# ControlMoteur_ESP32.net
KiCad netlist of a schematic drawn in EasyEDA
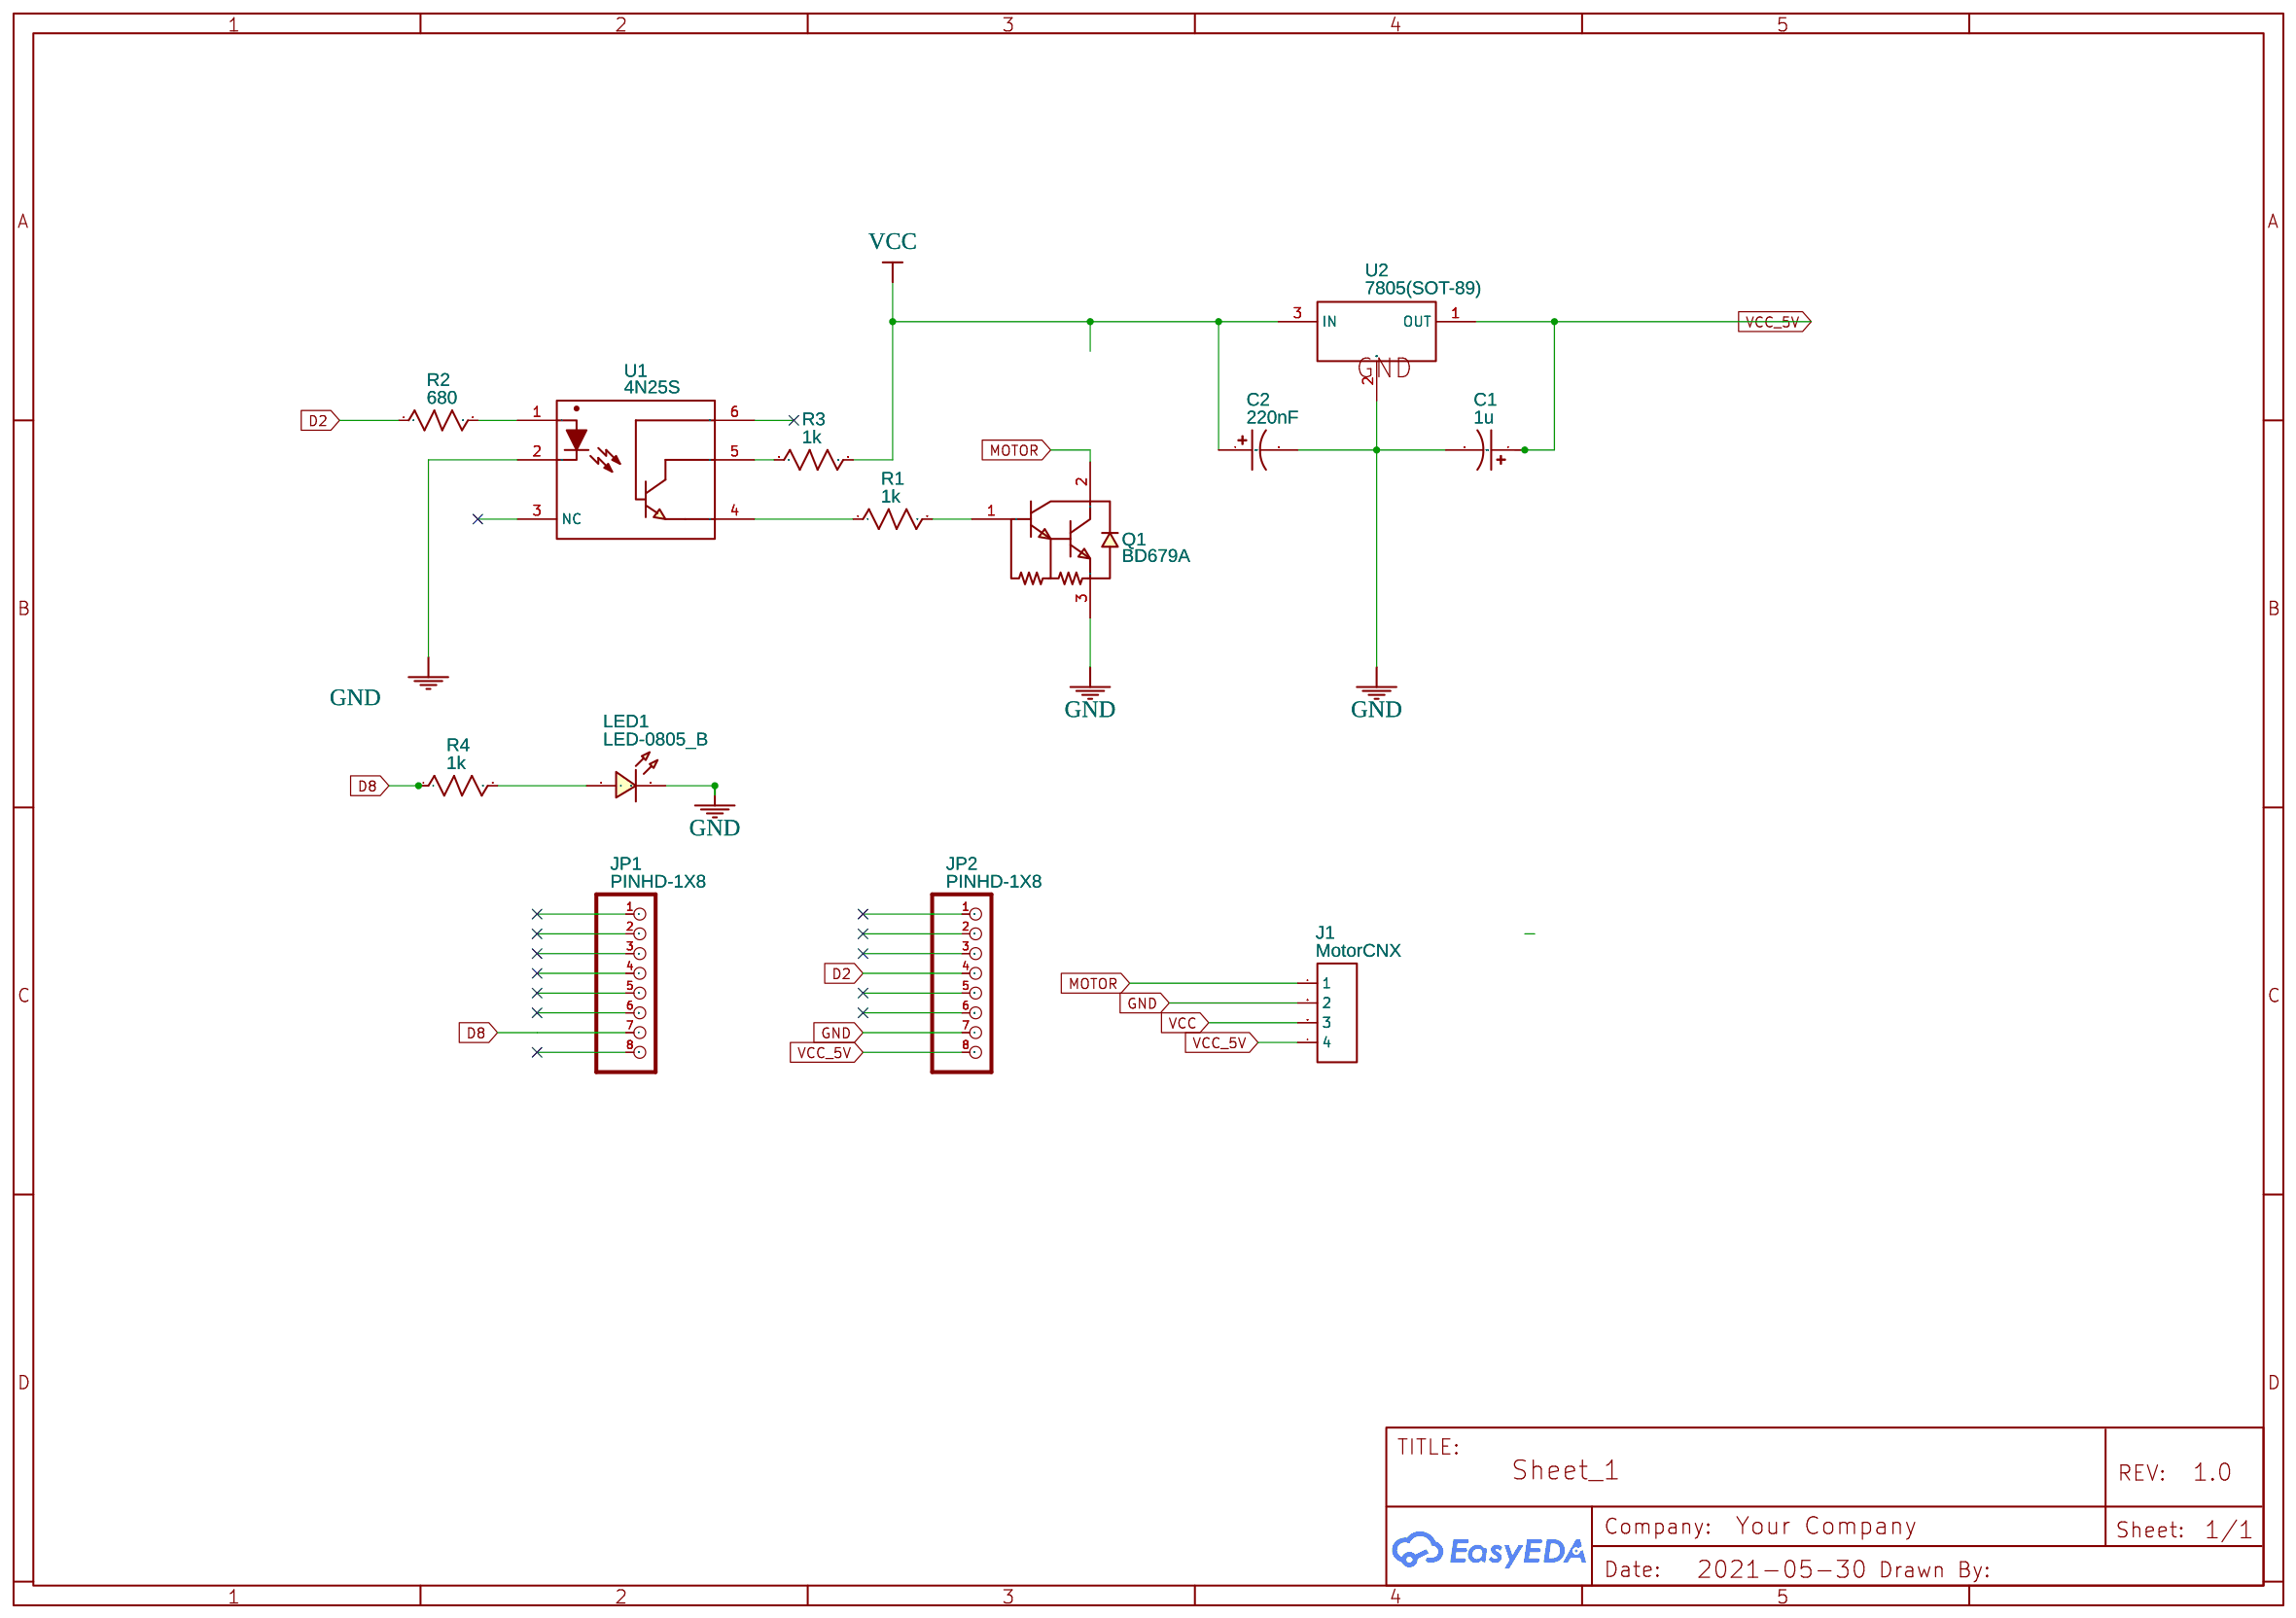
[diagram p0: schematic sheet]

(export (version "E")
  (design (tool "Eeschema 10.0.6"))
  (components
    (comp (ref "C1") (value "1u") (libsource (lib "") (part "C_Tan_SMD_A_US_1")))
    (comp (ref "C2") (value "220nF") (libsource (lib "") (part "C_Tan_SMD_A_US")))
    (comp (ref "J1")
      (value "MotorCNX")
      (fields (field (name "BOM_Supplier Part") "C124378"))
      (libsource (lib "") (part "HDR-M-2.54_1x4"))
    )
    (comp (ref "JP1")
      (value "PINHD-1X8")
      (fields (field (name "BOM_Supplier Part") "C492407"))
      (libsource (lib "") (part "PINHD-1X8"))
    )
    (comp (ref "JP2")
      (value "PINHD-1X8")
      (fields (field (name "BOM_Supplier Part") "C492407"))
      (libsource (lib "") (part "PINHD-1X8"))
    )
    (comp (ref "LED1")
      (value "LED-0805_B")
      (fields
        (field (name "BOM_Manufacturer Part") "D-B080508B1-KS2")
        (field (name "BOM_Supplier Part") "C108412")
      )
      (libsource (lib "") (part "LED-0805_B"))
    )
    (comp (ref "Q1")
      (value "BD679A")
      (fields (field (name "BOM_Supplier Part") "C2760771"))
      (libsource (lib "") (part "BD679A"))
    )
    (comp (ref "R1") (value "1k") (libsource (lib "") (part "R_1210_US")))
    (comp (ref "R2") (value "680") (libsource (lib "") (part "R_1210_US")))
    (comp (ref "R3") (value "1k") (libsource (lib "") (part "R_1210_US")))
    (comp (ref "R4") (value "1k") (libsource (lib "") (part "R_1210_US")))
    (comp (ref "U1")
      (value "4N25S")
      (fields (field (name "BOM_Supplier Part") "C143074"))
      (libsource (lib "") (part "4N25S"))
    )
    (comp (ref "U2")
      (value "7805(SOT-89)")
      (fields (field (name "BOM_Manufacturer Part") "CJ78L05") (field (name "BOM_Supplier Part") "C2079"))
      (libsource (lib "") (part "7805(SOT-89)"))
    )
  )
  (nets
    (net (code "1") (name "D2") (class "Default")
      (node (ref "JP2") (pin "4") (pinfunction "4_4") (pintype "unspecified"))
      (node (ref "R2") (pin "1") (pinfunction "1_1") (pintype "unspecified"))
    )
    (net (code "2") (name "D8") (class "Default")
      (node (ref "JP1") (pin "7") (pinfunction "7_7") (pintype "unspecified"))
      (node (ref "R4") (pin "1") (pinfunction "1_1") (pintype "unspecified"))
    )
    (net (code "3") (name "GND") (class "Default")
      (node (ref "C1") (pin "2") (pinfunction "2_2") (pintype "unspecified"))
      (node (ref "C2") (pin "2") (pinfunction "2_2") (pintype "unspecified"))
      (node (ref "J1") (pin "2") (pinfunction "2_2") (pintype "unspecified"))
      (node (ref "JP2") (pin "7") (pinfunction "7_7") (pintype "unspecified"))
      (node (ref "LED1") (pin "2") (pinfunction "2_2") (pintype "unspecified"))
      (node (ref "Q1") (pin "3") (pinfunction "E_3") (pintype "unspecified"))
      (node (ref "U1") (pin "2") (pinfunction "CAT_2") (pintype "unspecified"))
      (node (ref "U2") (pin "2") (pinfunction "GND_2") (pintype "passive"))
    )
    (net (code "4") (name "MOTOR") (class "Default")
      (node (ref "J1") (pin "1") (pinfunction "1_1") (pintype "unspecified"))
      (node (ref "Q1") (pin "2") (pinfunction "C_2") (pintype "unspecified"))
    )
    (net (code "5") (name "Net-(LED1-Pad1)") (class "Default")
      (node (ref "LED1") (pin "1") (pinfunction "1_1") (pintype "unspecified"))
      (node (ref "R4") (pin "2") (pinfunction "2_2") (pintype "unspecified"))
    )
    (net (code "6") (name "Net-(Q1-B)") (class "Default")
      (node (ref "Q1") (pin "1") (pinfunction "B_1") (pintype "unspecified"))
      (node (ref "R1") (pin "2") (pinfunction "2_2") (pintype "unspecified"))
    )
    (net (code "7") (name "Net-(R1-Pad1)") (class "Default")
      (node (ref "R1") (pin "1") (pinfunction "1_1") (pintype "unspecified"))
      (node (ref "U1") (pin "4") (pinfunction "4_4") (pintype "unspecified"))
    )
    (net (code "8") (name "Net-(R2-Pad2)") (class "Default")
      (node (ref "R2") (pin "2") (pinfunction "2_2") (pintype "unspecified"))
      (node (ref "U1") (pin "1") (pinfunction "1_1") (pintype "unspecified"))
    )
    (net (code "9") (name "Net-(U1-GND)") (class "Default")
      (node (ref "R3") (pin "1") (pinfunction "1_1") (pintype "unspecified"))
      (node (ref "U1") (pin "5") (pinfunction "GND_5") (pintype "unspecified"))
    )
    (net (code "10") (name "VCC") (class "Default")
      (node (ref "C2") (pin "1") (pinfunction "1_1") (pintype "unspecified"))
      (node (ref "J1") (pin "3") (pinfunction "3_3") (pintype "unspecified"))
      (node (ref "R3") (pin "2") (pinfunction "2_2") (pintype "unspecified"))
      (node (ref "U2") (pin "3") (pinfunction "IN_3") (pintype "passive"))
    )
    (net (code "11") (name "VCC_5V") (class "Default")
      (node (ref "C1") (pin "1") (pinfunction "1_1") (pintype "unspecified"))
      (node (ref "J1") (pin "4") (pinfunction "4_4") (pintype "unspecified"))
      (node (ref "JP2") (pin "8") (pinfunction "8_8") (pintype "unspecified"))
      (node (ref "U2") (pin "1") (pinfunction "OUT_1") (pintype "passive"))
    )
    (net (code "12") (name "unconnected-(JP1-Pad1)") (class "Default")
      (node (ref "JP1") (pin "1") (pinfunction "1_1") (pintype "unspecified+no_connect"))
    )
    (net (code "13") (name "unconnected-(JP1-Pad2)") (class "Default")
      (node (ref "JP1") (pin "2") (pinfunction "2_2") (pintype "unspecified+no_connect"))
    )
    (net (code "14") (name "unconnected-(JP1-Pad3)") (class "Default")
      (node (ref "JP1") (pin "3") (pinfunction "3_3") (pintype "unspecified+no_connect"))
    )
    (net (code "15") (name "unconnected-(JP1-Pad4)") (class "Default")
      (node (ref "JP1") (pin "4") (pinfunction "4_4") (pintype "unspecified+no_connect"))
    )
    (net (code "16") (name "unconnected-(JP1-Pad5)") (class "Default")
      (node (ref "JP1") (pin "5") (pinfunction "5_5") (pintype "unspecified+no_connect"))
    )
    (net (code "17") (name "unconnected-(JP1-Pad6)") (class "Default")
      (node (ref "JP1") (pin "6") (pinfunction "6_6") (pintype "unspecified+no_connect"))
    )
    (net (code "18") (name "unconnected-(JP1-Pad8)") (class "Default")
      (node (ref "JP1") (pin "8") (pinfunction "8_8") (pintype "unspecified+no_connect"))
    )
    (net (code "19") (name "unconnected-(JP2-Pad1)") (class "Default")
      (node (ref "JP2") (pin "1") (pinfunction "1_1") (pintype "unspecified+no_connect"))
    )
    (net (code "20") (name "unconnected-(JP2-Pad2)") (class "Default")
      (node (ref "JP2") (pin "2") (pinfunction "2_2") (pintype "unspecified+no_connect"))
    )
    (net (code "21") (name "unconnected-(JP2-Pad3)") (class "Default")
      (node (ref "JP2") (pin "3") (pinfunction "3_3") (pintype "unspecified+no_connect"))
    )
    (net (code "22") (name "unconnected-(JP2-Pad5)") (class "Default")
      (node (ref "JP2") (pin "5") (pinfunction "5_5") (pintype "unspecified+no_connect"))
    )
    (net (code "23") (name "unconnected-(JP2-Pad6)") (class "Default")
      (node (ref "JP2") (pin "6") (pinfunction "6_6") (pintype "unspecified+no_connect"))
    )
    (net (code "24") (name "unconnected-(U1-NC-Pad3)") (class "Default")
      (node (ref "U1") (pin "3") (pinfunction "NC_3") (pintype "unspecified+no_connect"))
    )
    (net (code "25") (name "unconnected-(U1-VO-Pad6)") (class "Default")
      (node (ref "U1") (pin "6") (pinfunction "VO_6") (pintype "unspecified+no_connect"))
    )
  )
)
